# IMU_Sensor.net
KiCad netlist of a schematic drawn in Altium Designer
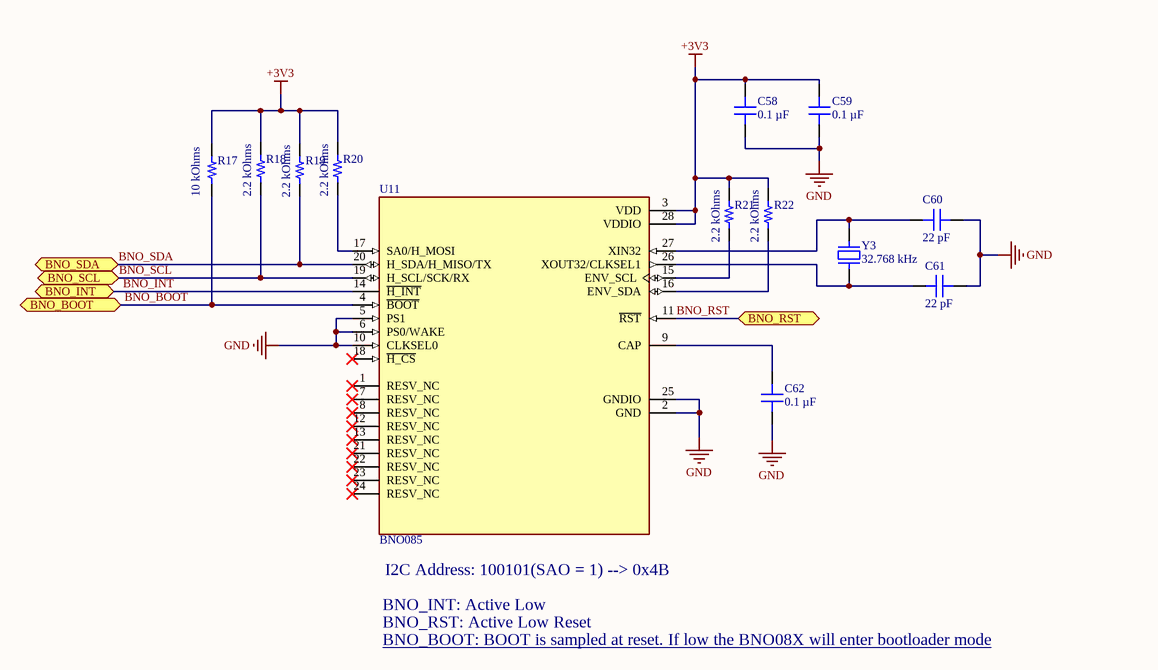
[diagram p0: IMU_Sensor.SchDoc]

(export (version "E")
  (design (tool "Eeschema 10.0.6"))
  (components
    (comp (ref "C58")
      (value "0.1 µF")
      (footprint "CAP 0402_1005")
      (description "CAP CER 0.1UF 6.3V X5R 0402")
      (fields
        (field (name "PART NUMBER") "C0402C104M9PAC7867")
        (field (name "CAPACITANCE") "0.1 µF")
        (field (name "MANUFACTURER") "KEMET")
      )
      (libsource (lib "Celestial Altium Library - altium_library") (part "Capacitor"))
    )
    (comp (ref "C59")
      (value "0.1 µF")
      (footprint "CAP 0402_1005")
      (description "CAP CER 0.1UF 6.3V X5R 0402")
      (fields
        (field (name "PART NUMBER") "C0402C104M9PAC7867")
        (field (name "CAPACITANCE") "0.1 µF")
        (field (name "MANUFACTURER") "KEMET")
      )
      (libsource (lib "Celestial Altium Library - altium_library") (part "Capacitor"))
    )
    (comp (ref "C60")
      (value "22 pF")
      (footprint "CAP 0603_1608")
      (description "CAP CER 22PF 10V NP0 0603")
      (fields
        (field (name "PART NUMBER") "C0603C220K8GAC7867")
        (field (name "CAPACITANCE") "22 pF")
        (field (name "MANUFACTURER") "KEMET")
      )
      (libsource (lib "Celestial Altium Library - altium_library") (part "Capacitor"))
    )
    (comp (ref "C61")
      (value "22 pF")
      (footprint "CAP 0603_1608")
      (description "CAP CER 22PF 10V NP0 0603")
      (fields
        (field (name "PART NUMBER") "C0603C220K8GAC7867")
        (field (name "CAPACITANCE") "22 pF")
        (field (name "MANUFACTURER") "KEMET")
      )
      (libsource (lib "Celestial Altium Library - altium_library") (part "Capacitor"))
    )
    (comp (ref "C62")
      (value "0.1 µF")
      (footprint "CAP 0402_1005")
      (description "CAP CER 0.1UF 6.3V X5R 0402")
      (fields
        (field (name "PART NUMBER") "C0402C104M9PAC7867")
        (field (name "CAPACITANCE") "0.1 µF")
        (field (name "MANUFACTURER") "KEMET")
      )
      (libsource (lib "Celestial Altium Library - altium_library") (part "Capacitor"))
    )
    (comp (ref "R17")
      (value "10 kOhms")
      (footprint "RES 0402_1005")
      (description "RES 10K OHM 0.1% 1/16W 0402")
      (fields (field (name "PART NUMBER") "TNPW040210K0BEED") (field (name "MANUFACTURER") "Vishay Dale"))
      (libsource (lib "Celestial Altium Library - altium_library") (part "Resistor"))
    )
    (comp (ref "R18")
      (value "2.2 kOhms")
      (footprint "YAGEO RES 0402_1005")
      (description "RES 2.2K OHM 1% 1/16W 0402")
      (fields (field (name "PART NUMBER") "RC0402FR-072K2L") (field (name "MANUFACTURER") "Yageo"))
      (libsource (lib "Celestial Altium Library - altium_library") (part "Resistor"))
    )
    (comp (ref "R19")
      (value "2.2 kOhms")
      (footprint "YAGEO RES 0402_1005")
      (description "RES 2.2K OHM 1% 1/16W 0402")
      (fields (field (name "PART NUMBER") "RC0402FR-072K2L") (field (name "MANUFACTURER") "Yageo"))
      (libsource (lib "Celestial Altium Library - altium_library") (part "Resistor"))
    )
    (comp (ref "R20")
      (value "2.2 kOhms")
      (footprint "YAGEO RES 0402_1005")
      (description "RES 2.2K OHM 1% 1/16W 0402")
      (fields (field (name "PART NUMBER") "RC0402FR-072K2L") (field (name "MANUFACTURER") "Yageo"))
      (libsource (lib "Celestial Altium Library - altium_library") (part "Resistor"))
    )
    (comp (ref "R21")
      (value "2.2 kOhms")
      (footprint "YAGEO RES 0402_1005")
      (description "RES 2.2K OHM 1% 1/16W 0402")
      (fields (field (name "PART NUMBER") "RC0402FR-072K2L") (field (name "MANUFACTURER") "Yageo"))
      (libsource (lib "Celestial Altium Library - altium_library") (part "Resistor"))
    )
    (comp (ref "R22")
      (value "2.2 kOhms")
      (footprint "YAGEO RES 0402_1005")
      (description "RES 2.2K OHM 1% 1/16W 0402")
      (fields (field (name "PART NUMBER") "RC0402FR-072K2L") (field (name "MANUFACTURER") "Yageo"))
      (libsource (lib "Celestial Altium Library - altium_library") (part "Resistor"))
    )
    (comp (ref "U11")
      (value "BNO085")
      (footprint "BNO085")
      (description "Accelerometer, Gyroscope, Magnetometer, 9 Axis Sensor I2C, SPI, UART Output")
      (fields (field (name "MANUFACTURER") "CEVA Technologies, Inc."))
      (libsource (lib "PCB_Lib") (part "BNO085"))
    )
    (comp (ref "Y3")
      (value "32.768 kHz")
      (footprint "ABRACON ABS06")
      (description "CRYSTAL 32.7680KHZ 12.5PF SMD")
      (fields (field (name "PART NUMBER") "ABS06-32.768KHZ-T") (field (name "MANUFACTURER") "Abracon LLC"))
      (libsource (lib "Celestial Altium Library - altium_library") (part "Abracon Crystal ABS06"))
    )
  )
  (nets
    (net (code "1") (name "+3V3") (class "Default")
      (node (ref "C58") (pin "2") (pinfunction "2_2") (pintype "passive"))
      (node (ref "C59") (pin "2") (pinfunction "2_2") (pintype "passive"))
      (node (ref "R17") (pin "2") (pinfunction "2_2") (pintype "passive"))
      (node (ref "R18") (pin "2") (pinfunction "2_2") (pintype "passive"))
      (node (ref "R19") (pin "2") (pinfunction "2_2") (pintype "passive"))
      (node (ref "R20") (pin "2") (pinfunction "2_2") (pintype "passive"))
      (node (ref "R21") (pin "2") (pinfunction "2_2") (pintype "passive"))
      (node (ref "R22") (pin "2") (pinfunction "2_2") (pintype "passive"))
      (node (ref "U11") (pin "28") (pinfunction "VDDIO_28") (pintype "power_in"))
      (node (ref "U11") (pin "3") (pinfunction "VDD_3") (pintype "power_in"))
    )
    (net (code "2") (name "/BNO_BOOT") (class "Default")
      (node (ref "R17") (pin "1") (pinfunction "1_1") (pintype "passive"))
      (node (ref "U11") (pin "4") (pinfunction "~{BOOT}_4") (pintype "input"))
    )
    (net (code "3") (name "/BNO_INT") (class "Default")
      (node (ref "U11") (pin "14") (pinfunction "~{H_INT}_14") (pintype "passive"))
    )
    (net (code "4") (name "/BNO_RST") (class "Default")
      (node (ref "U11") (pin "11") (pinfunction "~{RST}_11") (pintype "input"))
    )
    (net (code "5") (name "/BNO_SCL") (class "Default")
      (node (ref "R18") (pin "1") (pinfunction "1_1") (pintype "passive"))
      (node (ref "U11") (pin "19") (pinfunction "H_SCL/SCK/RX_19") (pintype "bidirectional"))
    )
    (net (code "6") (name "/BNO_SDA") (class "Default")
      (node (ref "R19") (pin "1") (pinfunction "1_1") (pintype "passive"))
      (node (ref "U11") (pin "20") (pinfunction "H_SDA/H_MISO/TX_20") (pintype "bidirectional"))
    )
    (net (code "7") (name "GND") (class "Default")
      (node (ref "C58") (pin "1") (pinfunction "1_1") (pintype "passive"))
      (node (ref "C59") (pin "1") (pinfunction "1_1") (pintype "passive"))
      (node (ref "C60") (pin "2") (pinfunction "2_2") (pintype "passive"))
      (node (ref "C61") (pin "2") (pinfunction "2_2") (pintype "passive"))
      (node (ref "C62") (pin "1") (pinfunction "1_1") (pintype "passive"))
      (node (ref "U11") (pin "10") (pinfunction "CLKSEL0_10") (pintype "input"))
      (node (ref "U11") (pin "2") (pinfunction "GND_2") (pintype "power_in"))
      (node (ref "U11") (pin "25") (pinfunction "GNDIO_25") (pintype "power_in"))
      (node (ref "U11") (pin "5") (pinfunction "PS1_5") (pintype "input"))
      (node (ref "U11") (pin "6") (pinfunction "PS0/WAKE_6") (pintype "input"))
    )
    (net (code "8") (name "Net-(U11-CAP)") (class "Default")
      (node (ref "C62") (pin "2") (pinfunction "2_2") (pintype "passive"))
      (node (ref "U11") (pin "9") (pinfunction "CAP_9") (pintype "passive"))
    )
    (net (code "9") (name "Net-(U11-ENV_SCL)") (class "Default")
      (node (ref "R21") (pin "1") (pinfunction "1_1") (pintype "passive"))
      (node (ref "U11") (pin "15") (pinfunction "ENV_SCL_15") (pintype "bidirectional"))
    )
    (net (code "10") (name "Net-(U11-ENV_SDA)") (class "Default")
      (node (ref "R22") (pin "1") (pinfunction "1_1") (pintype "passive"))
      (node (ref "U11") (pin "16") (pinfunction "ENV_SDA_16") (pintype "bidirectional"))
    )
    (net (code "11") (name "Net-(U11-SA0{slash}H_MOSI)") (class "Default")
      (node (ref "R20") (pin "1") (pinfunction "1_1") (pintype "passive"))
      (node (ref "U11") (pin "17") (pinfunction "SA0/H_MOSI_17") (pintype "input"))
    )
    (net (code "12") (name "Net-(U11-XIN32)") (class "Default")
      (node (ref "C60") (pin "1") (pinfunction "1_1") (pintype "passive"))
      (node (ref "U11") (pin "27") (pinfunction "XIN32_27") (pintype "input"))
      (node (ref "Y3") (pin "2") (pinfunction "2_2") (pintype "passive"))
    )
    (net (code "13") (name "Net-(U11-XOUT32{slash}CLKSEL1)") (class "Default")
      (node (ref "C61") (pin "1") (pinfunction "1_1") (pintype "passive"))
      (node (ref "U11") (pin "26") (pinfunction "XOUT32/CLKSEL1_26") (pintype "output"))
      (node (ref "Y3") (pin "1") (pinfunction "1_1") (pintype "passive"))
    )
    (net (code "14") (name "unconnected-(U11-RESV_NC-Pad1)") (class "Default")
      (node (ref "U11") (pin "1") (pinfunction "RESV_NC_1") (pintype "passive+no_connect"))
    )
    (net (code "15") (name "unconnected-(U11-RESV_NC-Pad7)") (class "Default")
      (node (ref "U11") (pin "7") (pinfunction "RESV_NC_7") (pintype "passive+no_connect"))
    )
    (net (code "16") (name "unconnected-(U11-RESV_NC-Pad8)") (class "Default")
      (node (ref "U11") (pin "8") (pinfunction "RESV_NC_8") (pintype "passive+no_connect"))
    )
    (net (code "17") (name "unconnected-(U11-RESV_NC-Pad12)") (class "Default")
      (node (ref "U11") (pin "12") (pinfunction "RESV_NC_12") (pintype "passive+no_connect"))
    )
    (net (code "18") (name "unconnected-(U11-RESV_NC-Pad13)") (class "Default")
      (node (ref "U11") (pin "13") (pinfunction "RESV_NC_13") (pintype "passive+no_connect"))
    )
    (net (code "19") (name "unconnected-(U11-RESV_NC-Pad21)") (class "Default")
      (node (ref "U11") (pin "21") (pinfunction "RESV_NC_21") (pintype "passive+no_connect"))
    )
    (net (code "20") (name "unconnected-(U11-RESV_NC-Pad22)") (class "Default")
      (node (ref "U11") (pin "22") (pinfunction "RESV_NC_22") (pintype "passive+no_connect"))
    )
    (net (code "21") (name "unconnected-(U11-RESV_NC-Pad23)") (class "Default")
      (node (ref "U11") (pin "23") (pinfunction "RESV_NC_23") (pintype "passive+no_connect"))
    )
    (net (code "22") (name "unconnected-(U11-RESV_NC-Pad24)") (class "Default")
      (node (ref "U11") (pin "24") (pinfunction "RESV_NC_24") (pintype "passive+no_connect"))
    )
    (net (code "23") (name "unconnected-(U11-~{H_CS}-Pad18)") (class "Default")
      (node (ref "U11") (pin "18") (pinfunction "~{H_CS}_18") (pintype "input+no_connect"))
    )
  )
)
